# 03_-_SCHEMATIC.net
KiCad netlist of a schematic drawn in Altium Designer
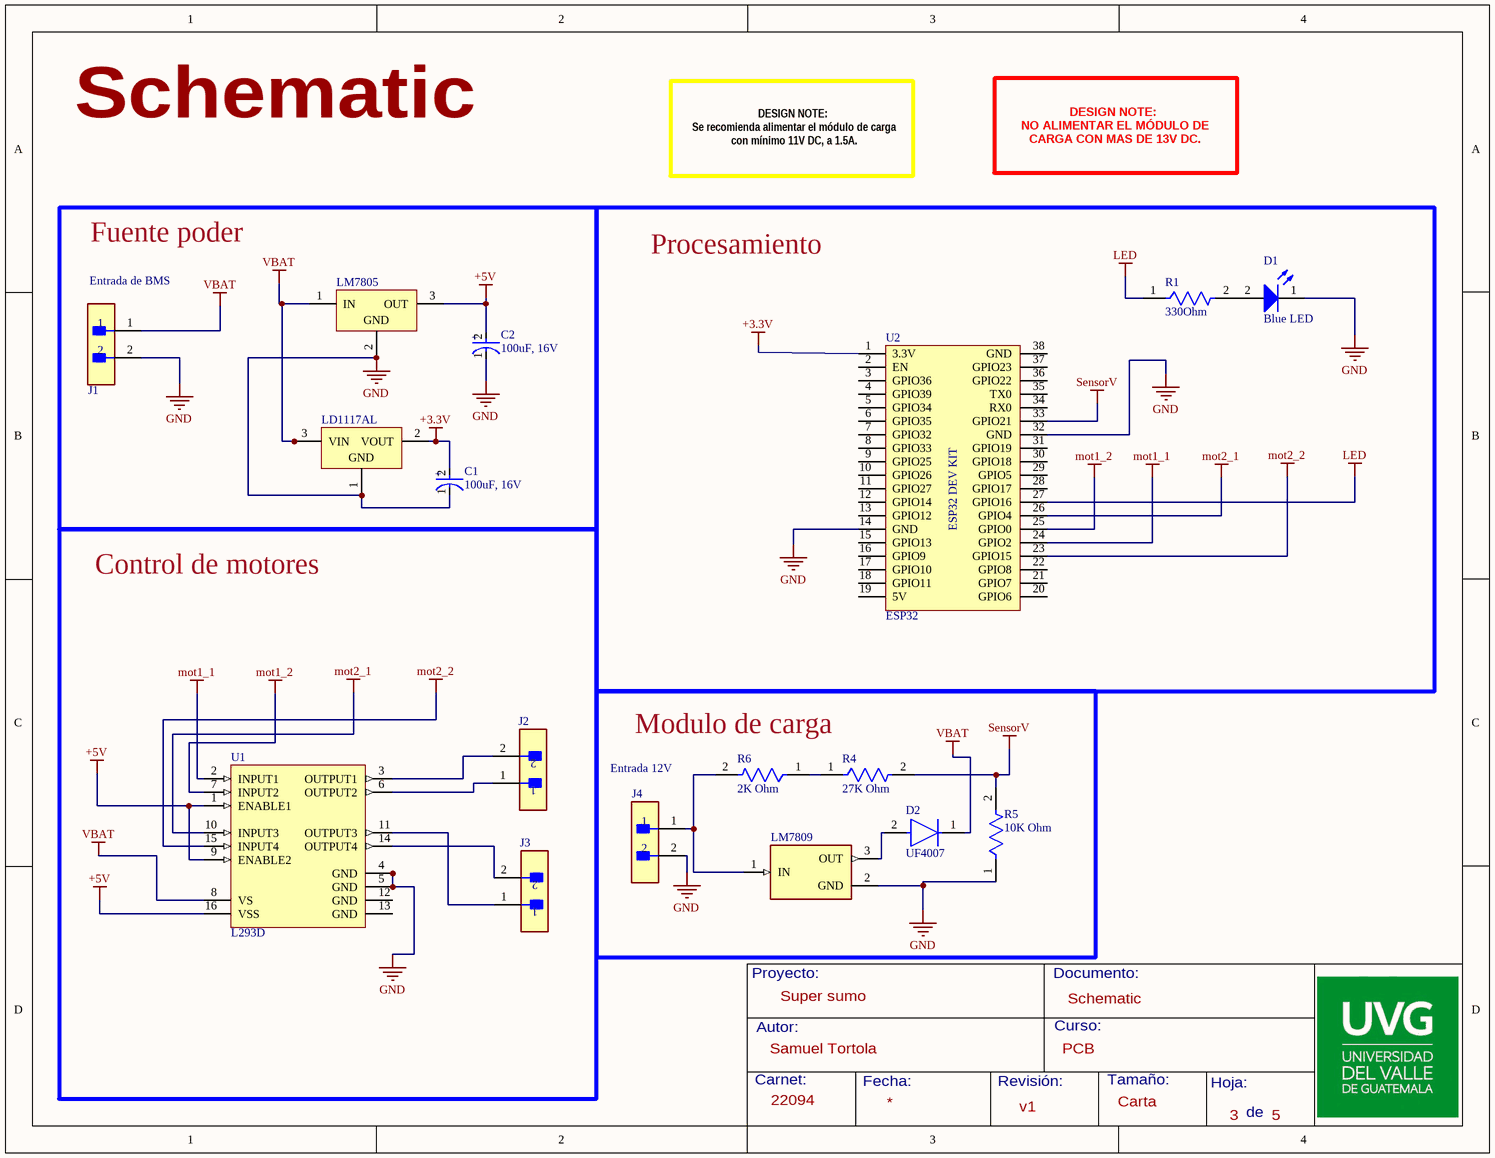
[diagram p0: [03] - SCHEMATIC.SchDoc]

(export (version "E")
  (design (tool "Eeschema 10.0.6"))
  (components
    (comp (ref "C1")
      (value "100uF, 16V")
      (footprint "FP-RAD-TH-D_6_3_0_5-L_7_1-MFG")
      (description "Aluminum Electrolytic Capacitors (Radial Lead Type) 100uF ±20% 16V")
      (fields (field (name "VOLTAGE") "16V") (field (name "TOLERANCE") "20%"))
      (libsource (lib "Altium Content Vault") (part "a00bbbee19879c290e62620ae7e47b1"))
    )
    (comp (ref "C2")
      (value "100uF, 16V")
      (footprint "FP-RAD-TH-D_6_3_0_5-L_7_1-MFG")
      (description "Aluminum Electrolytic Capacitors (Radial Lead Type) 100uF ±20% 16V")
      (fields (field (name "VOLTAGE") "16V") (field (name "TOLERANCE") "20%"))
      (libsource (lib "Altium Content Vault") (part "a00bbbee19879c290e62620ae7e47b1"))
    )
    (comp (ref "D1")
      (value "Blue LED")
      (footprint "WL-TMRW_D3.9H10.5")
      (libsource (lib "Altium Content Vault") (part "LED_Blue_2A-1K"))
    )
    (comp (ref "D2")
      (value "UF4007")
      (footprint "FP-017AH-MFG")
      (description "DIODE GEN PURP 1KV 1A DO41")
      (fields
        (field (name "MANUFACTURER") "ON Semiconductor")
        (field (name "OCTOPART") "https://octopart.com/uf4007-on+semiconductor-84331693")
      )
      (libsource (lib "Altium Content Vault") (part "d7152d700b627762746794eb795d46e"))
    )
    (comp (ref "J1")
      (value "B2B-EH-A(LF)(SN)")
      (footprint "FP-B2B-EH-A_LF_SN-MFG")
      (description "CONN HEADER VERT 2POS 2.5MM")
      (libsource (lib "") (part "3bc925449376181038e59eaffc5286c_1"))
    )
    (comp (ref "J2")
      (value "B2B-EH-A(LF)(SN)")
      (footprint "FP-B2B-EH-A_LF_SN-MFG")
      (description "CONN HEADER VERT 2POS 2.5MM")
      (libsource (lib "Altium Content Vault") (part "3bc925449376181038e59eaffc5286c"))
    )
    (comp (ref "J3")
      (value "B2B-EH-A(LF)(SN)")
      (footprint "FP-B2B-EH-A_LF_SN-MFG")
      (description "CONN HEADER VERT 2POS 2.5MM")
      (libsource (lib "Altium Content Vault") (part "3bc925449376181038e59eaffc5286c"))
    )
    (comp (ref "J4")
      (value "B2B-EH-A(LF)(SN)")
      (footprint "FP-B2B-EH-A_LF_SN-MFG")
      (description "CONN HEADER VERT 2POS 2.5MM")
      (libsource (lib "") (part "3bc925449376181038e59eaffc5286c_1"))
    )
    (comp (ref "LD1117AL")
      (value "LD1117V33C")
      (footprint "TO220")
      (description "Fixed Low Drop Positive Voltage Regulator, 3.3V, 3-Pin TO-220")
      (libsource (lib "Altium Content Vault") (part "PM-REG-LD1117V-SIL3"))
    )
    (comp (ref "LM7805")
      (value "LM7805")
      (footprint "TO220")
      (description "Positive Voltage Regulator, 5V, 3-Pin TO-220")
      (libsource (lib "LM7805") (part "LM7805"))
    )
    (comp (ref "LM7809")
      (value "LM7809CT")
      (footprint "TO254P470X1016X1879-3P")
      (description "Linear Voltage Regulator IC 1 Output 1A TO-220-3")
      (fields (field (name "MP") "LM7809C") (field (name "MF") "Fujitsu"))
      (libsource (lib "LM7809CT") (part "LM7809CT"))
    )
    (comp (ref "R1")
      (value "330Ohm")
      (footprint "FP-MRS25-MFG")
      (description "RES 953 OHM 0.6W 1% AXIAL")
      (fields (field (name "TOLERANCE") "1%"))
      (libsource (lib "Altium Content Vault") (part "1029c3af85768c4190bb7ad29bc67b5"))
    )
    (comp (ref "R4")
      (value "27K Ohm")
      (footprint "FP-MRS25-MFG")
      (description "RES 953 OHM 0.6W 1% AXIAL")
      (fields (field (name "TOLERANCE") "1%"))
      (libsource (lib "Altium Content Vault") (part "1029c3af85768c4190bb7ad29bc67b5"))
    )
    (comp (ref "R5")
      (value "10K Ohm")
      (footprint "FP-MRS25-MFG")
      (description "RES 953 OHM 0.6W 1% AXIAL")
      (fields (field (name "TOLERANCE") "1%"))
      (libsource (lib "Altium Content Vault") (part "1029c3af85768c4190bb7ad29bc67b5"))
    )
    (comp (ref "R6")
      (value "2K Ohm")
      (footprint "FP-MRS25-MFG")
      (description "RES 953 OHM 0.6W 1% AXIAL")
      (fields (field (name "TOLERANCE") "1%"))
      (libsource (lib "Altium Content Vault") (part "1029c3af85768c4190bb7ad29bc67b5"))
    )
    (comp (ref "U1")
      (value "L293D")
      (footprint "STM-L293D-16")
      (description "Push-Pull Four Channel Driver with Diode, 4.5 to 36 V, -40 to 150 degC, 16-Pin PDIP, RoHS, Tube")
      (fields (field (name "MANUFACTURER") "STMicroelectronics"))
      (libsource (lib "Altium Content Vault") (part "STM-L293D-16"))
    )
    (comp (ref "U2")
      (value "ESP32")
      (footprint "ESP32 DEV KIT")
      (description "ESP32 Depelopment version 38 pines")
      (libsource (lib "ESP32") (part "ESP32 Dev Module Kit"))
    )
  )
  (nets
    (net (code "1") (name "+3.3V") (class "Default")
      (node (ref "C1") (pin "2") (pinfunction "A_2") (pintype "passive"))
      (node (ref "LD1117AL") (pin "2") (pinfunction "VOUT_2") (pintype "power_in"))
      (node (ref "U2") (pin "1") (pinfunction "3.3V_1") (pintype "passive"))
    )
    (net (code "2") (name "+5V") (class "Default")
      (node (ref "C2") (pin "2") (pinfunction "A_2") (pintype "passive"))
      (node (ref "LM7805") (pin "3") (pinfunction "OUT_3") (pintype "power_in"))
      (node (ref "U1") (pin "1") (pinfunction "ENABLE1_1") (pintype "input"))
      (node (ref "U1") (pin "16") (pinfunction "VSS_16") (pintype "power_in"))
      (node (ref "U1") (pin "9") (pinfunction "ENABLE2_9") (pintype "input"))
    )
    (net (code "3") (name "GND") (class "Default")
      (node (ref "C1") (pin "1") (pinfunction "C_1") (pintype "passive"))
      (node (ref "C2") (pin "1") (pinfunction "C_1") (pintype "passive"))
      (node (ref "D1") (pin "1") (pinfunction "K_1") (pintype "passive"))
      (node (ref "J1") (pin "2") (pinfunction "2_2") (pintype "passive"))
      (node (ref "J4") (pin "2") (pinfunction "2_2") (pintype "passive"))
      (node (ref "LD1117AL") (pin "1") (pinfunction "GND_1") (pintype "power_in"))
      (node (ref "LM7805") (pin "2") (pinfunction "GND_2") (pintype "power_in"))
      (node (ref "LM7809") (pin "2") (pinfunction "GND_2") (pintype "power_in"))
      (node (ref "R5") (pin "1") (pinfunction "1_1") (pintype "passive"))
      (node (ref "U1") (pin "4") (pinfunction "GND_4") (pintype "power_in"))
      (node (ref "U1") (pin "5") (pinfunction "GND_5") (pintype "power_in"))
      (node (ref "U2") (pin "14") (pinfunction "GND_14") (pintype "passive"))
      (node (ref "U2") (pin "32") (pinfunction "GND_32") (pintype "passive"))
    )
    (net (code "4") (name "LED") (class "Default")
      (node (ref "R1") (pin "1") (pinfunction "1_1") (pintype "passive"))
      (node (ref "U2") (pin "27") (pinfunction "GPIO16_27") (pintype "passive"))
    )
    (net (code "5") (name "Net-(D1-A)") (class "Default")
      (node (ref "D1") (pin "2") (pinfunction "A_2") (pintype "passive"))
      (node (ref "R1") (pin "2") (pinfunction "2_2") (pintype "passive"))
    )
    (net (code "6") (name "Net-(D2-A)") (class "Default")
      (node (ref "D2") (pin "2") (pinfunction "A_2") (pintype "passive"))
      (node (ref "LM7809") (pin "3") (pinfunction "OUT_3") (pintype "output"))
    )
    (net (code "7") (name "Net-(LM7809-IN)") (class "Default")
      (node (ref "J4") (pin "1") (pinfunction "1_1") (pintype "passive"))
      (node (ref "LM7809") (pin "1") (pinfunction "IN_1") (pintype "input"))
      (node (ref "R6") (pin "2") (pinfunction "2_2") (pintype "passive"))
    )
    (net (code "8") (name "Net-(R4-Pad1)") (class "Default")
      (node (ref "R4") (pin "1") (pinfunction "1_1") (pintype "passive"))
      (node (ref "R6") (pin "1") (pinfunction "1_1") (pintype "passive"))
    )
    (net (code "9") (name "Net-(U1-OUTPUT1)") (class "Default")
      (node (ref "J2") (pin "2") (pinfunction "2_2") (pintype "passive"))
      (node (ref "U1") (pin "3") (pinfunction "OUTPUT1_3") (pintype "output"))
    )
    (net (code "10") (name "Net-(U1-OUTPUT2)") (class "Default")
      (node (ref "J2") (pin "1") (pinfunction "1_1") (pintype "passive"))
      (node (ref "U1") (pin "6") (pinfunction "OUTPUT2_6") (pintype "output"))
    )
    (net (code "11") (name "Net-(U1-OUTPUT3)") (class "Default")
      (node (ref "J3") (pin "1") (pinfunction "1_1") (pintype "passive"))
      (node (ref "U1") (pin "11") (pinfunction "OUTPUT3_11") (pintype "output"))
    )
    (net (code "12") (name "Net-(U1-OUTPUT4)") (class "Default")
      (node (ref "J3") (pin "2") (pinfunction "2_2") (pintype "passive"))
      (node (ref "U1") (pin "14") (pinfunction "OUTPUT4_14") (pintype "output"))
    )
    (net (code "13") (name "SensorV") (class "Default")
      (node (ref "R4") (pin "2") (pinfunction "2_2") (pintype "passive"))
      (node (ref "R5") (pin "2") (pinfunction "2_2") (pintype "passive"))
      (node (ref "U2") (pin "33") (pinfunction "GPIO21_33") (pintype "passive"))
    )
    (net (code "14") (name "VBAT") (class "Default")
      (node (ref "D2") (pin "1") (pinfunction "C_1") (pintype "passive"))
      (node (ref "J1") (pin "1") (pinfunction "1_1") (pintype "passive"))
      (node (ref "LD1117AL") (pin "3") (pinfunction "VIN_3") (pintype "power_in"))
      (node (ref "LM7805") (pin "1") (pinfunction "IN_1") (pintype "power_in"))
      (node (ref "U1") (pin "8") (pinfunction "VS_8") (pintype "power_in"))
    )
    (net (code "15") (name "mot1_1") (class "Default")
      (node (ref "U1") (pin "2") (pinfunction "INPUT1_2") (pintype "input"))
      (node (ref "U2") (pin "24") (pinfunction "GPIO2_24") (pintype "passive"))
    )
    (net (code "16") (name "mot1_2") (class "Default")
      (node (ref "U1") (pin "7") (pinfunction "INPUT2_7") (pintype "input"))
      (node (ref "U2") (pin "25") (pinfunction "GPIO0_25") (pintype "passive"))
    )
    (net (code "17") (name "mot2_1") (class "Default")
      (node (ref "U1") (pin "10") (pinfunction "INPUT3_10") (pintype "input"))
      (node (ref "U2") (pin "26") (pinfunction "GPIO4_26") (pintype "passive"))
    )
    (net (code "18") (name "mot2_2") (class "Default")
      (node (ref "U1") (pin "15") (pinfunction "INPUT4_15") (pintype "input"))
      (node (ref "U2") (pin "23") (pinfunction "GPIO15_23") (pintype "passive"))
    )
    (net (code "19") (name "unconnected-(U1-GND-Pad12)") (class "Default")
      (node (ref "U1") (pin "12") (pinfunction "GND_12") (pintype "power_in"))
    )
    (net (code "20") (name "unconnected-(U1-GND-Pad13)") (class "Default")
      (node (ref "U1") (pin "13") (pinfunction "GND_13") (pintype "power_in"))
    )
    (net (code "21") (name "unconnected-(U2-5V-Pad19)") (class "Default")
      (node (ref "U2") (pin "19") (pinfunction "5V_19") (pintype "passive"))
    )
    (net (code "22") (name "unconnected-(U2-EN-Pad2)") (class "Default")
      (node (ref "U2") (pin "2") (pinfunction "EN_2") (pintype "passive"))
    )
    (net (code "23") (name "unconnected-(U2-GND-Pad38)") (class "Default")
      (node (ref "U2") (pin "38") (pinfunction "GND_38") (pintype "passive"))
    )
    (net (code "24") (name "unconnected-(U2-GPIO5-Pad29)") (class "Default")
      (node (ref "U2") (pin "29") (pinfunction "GPIO5_29") (pintype "passive"))
    )
    (net (code "25") (name "unconnected-(U2-GPIO6-Pad20)") (class "Default")
      (node (ref "U2") (pin "20") (pinfunction "GPIO6_20") (pintype "passive"))
    )
    (net (code "26") (name "unconnected-(U2-GPIO7-Pad21)") (class "Default")
      (node (ref "U2") (pin "21") (pinfunction "GPIO7_21") (pintype "passive"))
    )
    (net (code "27") (name "unconnected-(U2-GPIO8-Pad22)") (class "Default")
      (node (ref "U2") (pin "22") (pinfunction "GPIO8_22") (pintype "passive"))
    )
    (net (code "28") (name "unconnected-(U2-GPIO9-Pad16)") (class "Default")
      (node (ref "U2") (pin "16") (pinfunction "GPIO9_16") (pintype "passive"))
    )
    (net (code "29") (name "unconnected-(U2-GPIO10-Pad17)") (class "Default")
      (node (ref "U2") (pin "17") (pinfunction "GPIO10_17") (pintype "passive"))
    )
    (net (code "30") (name "unconnected-(U2-GPIO11-Pad18)") (class "Default")
      (node (ref "U2") (pin "18") (pinfunction "GPIO11_18") (pintype "passive"))
    )
    (net (code "31") (name "unconnected-(U2-GPIO12-Pad13)") (class "Default")
      (node (ref "U2") (pin "13") (pinfunction "GPIO12_13") (pintype "passive"))
    )
    (net (code "32") (name "unconnected-(U2-GPIO13-Pad15)") (class "Default")
      (node (ref "U2") (pin "15") (pinfunction "GPIO13_15") (pintype "passive"))
    )
    (net (code "33") (name "unconnected-(U2-GPIO14-Pad12)") (class "Default")
      (node (ref "U2") (pin "12") (pinfunction "GPIO14_12") (pintype "passive"))
    )
    (net (code "34") (name "unconnected-(U2-GPIO17-Pad28)") (class "Default")
      (node (ref "U2") (pin "28") (pinfunction "GPIO17_28") (pintype "passive"))
    )
    (net (code "35") (name "unconnected-(U2-GPIO18-Pad30)") (class "Default")
      (node (ref "U2") (pin "30") (pinfunction "GPIO18_30") (pintype "passive"))
    )
    (net (code "36") (name "unconnected-(U2-GPIO19-Pad31)") (class "Default")
      (node (ref "U2") (pin "31") (pinfunction "GPIO19_31") (pintype "passive"))
    )
    (net (code "37") (name "unconnected-(U2-GPIO22-Pad36)") (class "Default")
      (node (ref "U2") (pin "36") (pinfunction "GPIO22_36") (pintype "passive"))
    )
    (net (code "38") (name "unconnected-(U2-GPIO23-Pad37)") (class "Default")
      (node (ref "U2") (pin "37") (pinfunction "GPIO23_37") (pintype "passive"))
    )
    (net (code "39") (name "unconnected-(U2-GPIO25-Pad9)") (class "Default")
      (node (ref "U2") (pin "9") (pinfunction "GPIO25_9") (pintype "passive"))
    )
    (net (code "40") (name "unconnected-(U2-GPIO26-Pad10)") (class "Default")
      (node (ref "U2") (pin "10") (pinfunction "GPIO26_10") (pintype "passive"))
    )
    (net (code "41") (name "unconnected-(U2-GPIO27-Pad11)") (class "Default")
      (node (ref "U2") (pin "11") (pinfunction "GPIO27_11") (pintype "passive"))
    )
    (net (code "42") (name "unconnected-(U2-GPIO32-Pad7)") (class "Default")
      (node (ref "U2") (pin "7") (pinfunction "GPIO32_7") (pintype "passive"))
    )
    (net (code "43") (name "unconnected-(U2-GPIO33-Pad8)") (class "Default")
      (node (ref "U2") (pin "8") (pinfunction "GPIO33_8") (pintype "passive"))
    )
    (net (code "44") (name "unconnected-(U2-GPIO34-Pad5)") (class "Default")
      (node (ref "U2") (pin "5") (pinfunction "GPIO34_5") (pintype "passive"))
    )
    (net (code "45") (name "unconnected-(U2-GPIO35-Pad6)") (class "Default")
      (node (ref "U2") (pin "6") (pinfunction "GPIO35_6") (pintype "passive"))
    )
    (net (code "46") (name "unconnected-(U2-GPIO36-Pad3)") (class "Default")
      (node (ref "U2") (pin "3") (pinfunction "GPIO36_3") (pintype "passive"))
    )
    (net (code "47") (name "unconnected-(U2-GPIO39-Pad4)") (class "Default")
      (node (ref "U2") (pin "4") (pinfunction "GPIO39_4") (pintype "passive"))
    )
    (net (code "48") (name "unconnected-(U2-RX0-Pad34)") (class "Default")
      (node (ref "U2") (pin "34") (pinfunction "RX0_34") (pintype "passive"))
    )
    (net (code "49") (name "unconnected-(U2-TX0-Pad35)") (class "Default")
      (node (ref "U2") (pin "35") (pinfunction "TX0_35") (pintype "passive"))
    )
  )
)
